# MCU.net
KiCad netlist of a schematic drawn in Altium Designer
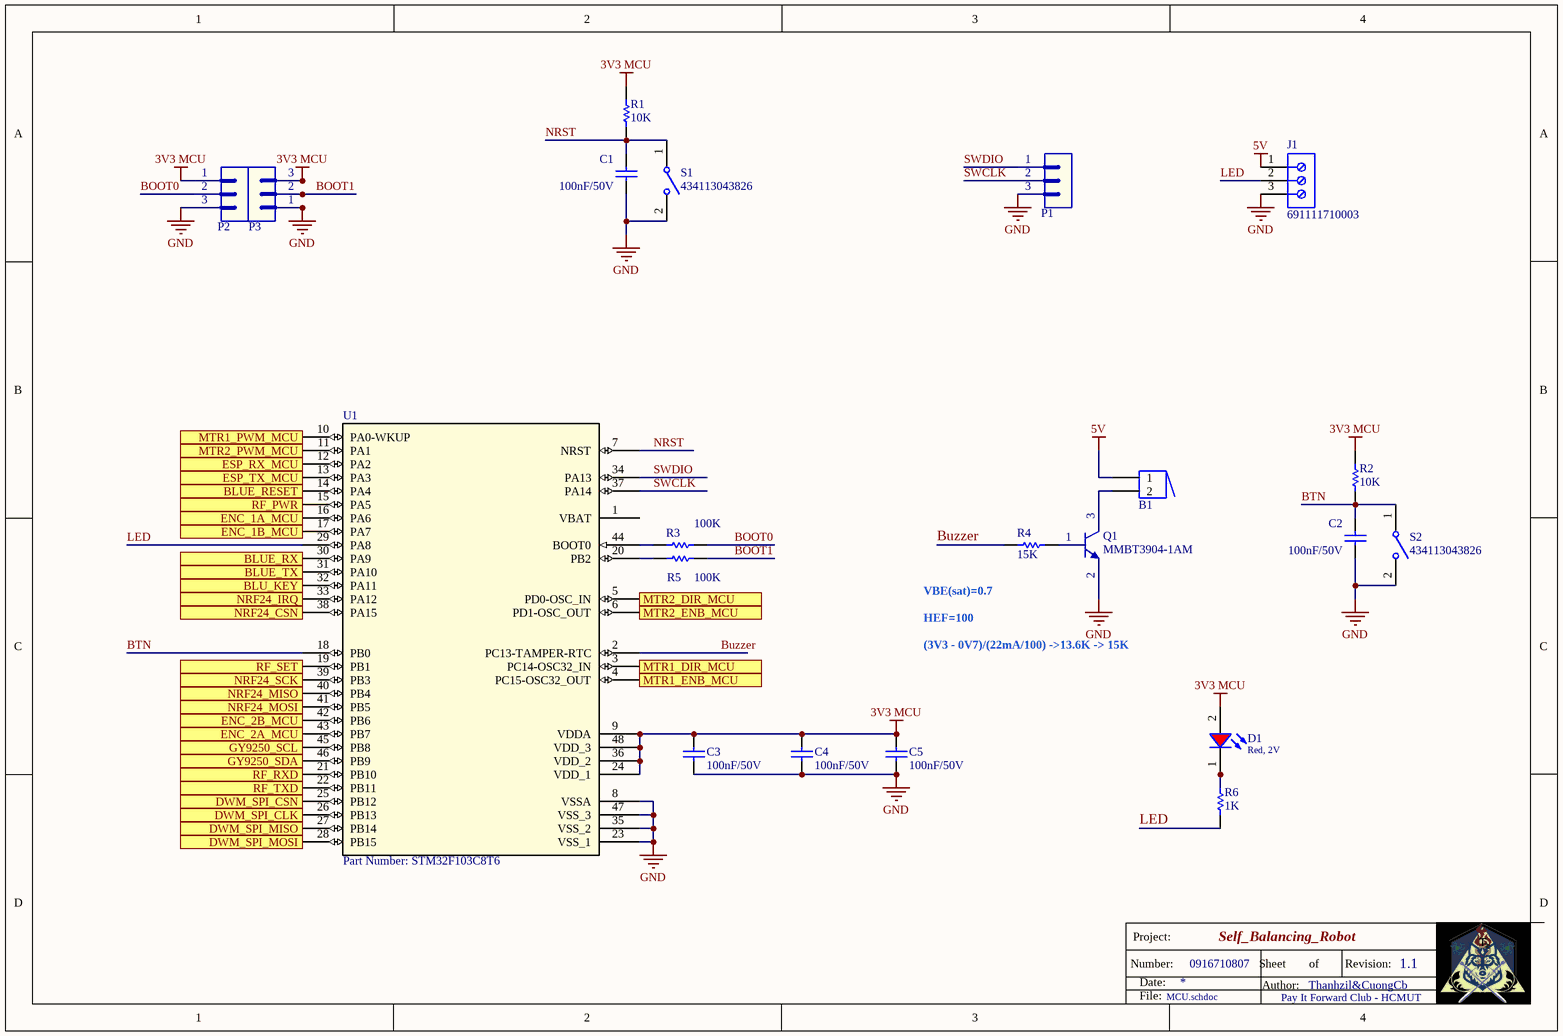
[diagram p0: MCU.SchDoc]

(export (version "E")
  (design (tool "Eeschema 10.0.6"))
  (components
    (comp (ref "B1")
      (value "Buzzer")
      (footprint "BUZZER")
      (libsource (lib "PIF_Schematic_Lib") (part "Buzzer"))
    )
    (comp (ref "C1")
      (value "100nF/50V")
      (footprint "CAP-SM-0805")
      (description "CAP CER 0.1UF 50V Y5V 0805")
      (fields
        (field (name "MANUFACTURER") "Samsung Electro-Mechanics")
        (field (name "MANUFACTURER PART NUMBER") "CL21F104ZBCNNNC")
      )
      (libsource (lib "Capacitor") (part "Cap-100nF-50V-0805"))
    )
    (comp (ref "C2")
      (value "100nF/50V")
      (footprint "CAP-SM-0805")
      (description "CAP CER 0.1UF 50V Y5V 0805")
      (fields
        (field (name "MANUFACTURER") "Samsung Electro-Mechanics")
        (field (name "MANUFACTURER PART NUMBER") "CL21F104ZBCNNNC")
      )
      (libsource (lib "Capacitor") (part "Cap-100nF-50V-0805"))
    )
    (comp (ref "C3")
      (value "100nF/50V")
      (footprint "CAP-SM-0805")
      (description "CAP CER 0.1UF 50V Y5V 0805")
      (fields
        (field (name "MANUFACTURER") "Samsung Electro-Mechanics")
        (field (name "MANUFACTURER PART NUMBER") "CL21F104ZBCNNNC")
      )
      (libsource (lib "Capacitor") (part "Cap-100nF-50V-0805"))
    )
    (comp (ref "C4")
      (value "100nF/50V")
      (footprint "CAP-SM-0805")
      (description "CAP CER 0.1UF 50V Y5V 0805")
      (fields
        (field (name "MANUFACTURER") "Samsung Electro-Mechanics")
        (field (name "MANUFACTURER PART NUMBER") "CL21F104ZBCNNNC")
      )
      (libsource (lib "Capacitor") (part "Cap-100nF-50V-0805"))
    )
    (comp (ref "C5")
      (value "100nF/50V")
      (footprint "CAP-SM-0805")
      (description "CAP CER 0.1UF 50V Y5V 0805")
      (fields
        (field (name "MANUFACTURER") "Samsung Electro-Mechanics")
        (field (name "MANUFACTURER PART NUMBER") "CL21F104ZBCNNNC")
      )
      (libsource (lib "Capacitor") (part "Cap-100nF-50V-0805"))
    )
    (comp (ref "D1")
      (value "Red, 2V")
      (footprint "WL-SMCW_0805")
      (description "WL-SMCW SMT Mono-color Chip LED Waterclear, size 0805, Red, 2V, 140deg")
      (fields (field (name "PART NUMBER") "150080RS75000") (field (name "PUBLISHER") "Wurth Elektronik"))
      (libsource (lib "LED_150060BS75000_Altium_WL-SMCW_rev20a") (part "150080RS75000"))
    )
    (comp (ref "J1")
      (value "691111710003")
      (footprint "Project_Xe_Can_Bang:691111710003")
      (description "WR-TBL Serie 111 Horizontal Entry Modular, Pressure Clamp, pitch 5mm, 3p")
      (fields (field (name "PUBLISHER") "Wurth Elektronik"))
      (libsource (lib "Project_Xe_Can_Bang") (part "691111710003"))
    )
    (comp (ref "P1")
      (value "Header 3")
      (footprint "Project_Xe_Can_Bang:JP3")
      (description "Header, 3-Pin")
      (fields (field (name "PUBLISHER") "Altium Limited"))
      (libsource (lib "Project_Xe_Can_Bang") (part "Header 3"))
    )
    (comp (ref "P2")
      (value "Header 3")
      (footprint "JP3")
      (description "Header, 3-Pin")
      (fields (field (name "PUBLISHER") "Altium Limited"))
      (libsource (lib "Header-connector") (part "Header 3"))
    )
    (comp (ref "P3")
      (value "Header 3")
      (footprint "JP3")
      (description "Header, 3-Pin")
      (fields (field (name "PUBLISHER") "Altium Limited"))
      (libsource (lib "") (part "Header 3_1"))
    )
    (comp (ref "Q1")
      (value "MMBT3904-1AM")
      (footprint "SOT23_NEX")
      (libsource (lib "BJT") (part "MMBT3904-1AM"))
    )
    (comp (ref "R1")
      (value "10K")
      (footprint "Resistor:RES-SM-0805")
      (description "RES 10K OHM 1% 1/4W 0805")
      (fields
        (field (name "MANUFACTURER") "Stackpole Electronics Inc")
        (field (name "MANUFACTURER PART NUMBER") "RNCP0805FTD10K0")
      )
      (libsource (lib "Resistor") (part "Res-10k-0805"))
    )
    (comp (ref "R2")
      (value "10K")
      (footprint "Resistor:RES-SM-0805")
      (description "RES 10K OHM 1% 1/4W 0805")
      (fields
        (field (name "MANUFACTURER") "Stackpole Electronics Inc")
        (field (name "MANUFACTURER PART NUMBER") "RNCP0805FTD10K0")
      )
      (libsource (lib "Resistor") (part "Res-10k-0805"))
    )
    (comp (ref "R3")
      (value "100K")
      (footprint "Resistor:RES-SM-0805")
      (description "RES 0 OHM JUMPER 0805")
      (fields
        (field (name "MANUFACTURER") "Vishay Dale")
        (field (name "MANUFACTURER PART NUMBER") "WSL080500000ZEA9")
      )
      (libsource (lib "Resistor") (part "Res-100K-0805"))
    )
    (comp (ref "R4")
      (value "15K")
      (footprint "Resistor:RES-SM-0805")
      (description "RES 15K OHM 1% 1/4W 0805")
      (fields
        (field (name "MANUFACTURER") "TE Connectivity Passive Product")
        (field (name "MANUFACTURER PART NUMBER") "CRGCQ0805F15K")
      )
      (libsource (lib "Resistor") (part "Res-15K-0805"))
    )
    (comp (ref "R5")
      (value "100K")
      (footprint "Resistor:RES-SM-0805")
      (description "RES 0 OHM JUMPER 0805")
      (fields
        (field (name "MANUFACTURER") "Vishay Dale")
        (field (name "MANUFACTURER PART NUMBER") "WSL080500000ZEA9")
      )
      (libsource (lib "Resistor") (part "Res-100K-0805"))
    )
    (comp (ref "R6")
      (value "1K")
      (footprint "Resistor:RES-SM-0805")
      (description "RES 1K OHM 1% 1/4W 0805")
      (fields
        (field (name "MANUFACTURER") "Stackpole Electronics Inc")
        (field (name "MANUFACTURER PART NUMBER") "RNCP0805FTD1K00")
      )
      (libsource (lib "Resistor") (part "Res-1K-0805"))
    )
    (comp (ref "S1")
      (value "434113043826")
      (footprint "434113043826")
      (description "WS-TASV J-Bend SMT Tact Switch 6x3.5mm, height 4.3mm, 260gf")
      (fields (field (name "PUBLISHER") "Wurth Elektronik"))
      (libsource (lib "434113043826_Altium_WS-TASV_rev20a") (part "434113043826"))
    )
    (comp (ref "S2")
      (value "434113043826")
      (footprint "434113043826")
      (description "WS-TASV J-Bend SMT Tact Switch 6x3.5mm, height 4.3mm, 260gf")
      (fields (field (name "PUBLISHER") "Wurth Elektronik"))
      (libsource (lib "434113043826_Altium_WS-TASV_rev20a") (part "434113043826"))
    )
    (comp (ref "U1")
      (value "Part Number: STM32F103C8T6")
      (footprint "Project_Xe_Can_Bang:LQFP - 48")
      (fields
        (field (name "MANUFACTURER_PART_NUMBER") "STM32F103C8T6")
        (field (name "COPYRIGHT") "Copyright (C) 2018 Accelerated Designs. All rights reserved")
      )
      (libsource (lib "Project_Xe_Can_Bang") (part "STM32F103C8T6"))
    )
  )
  (nets
    (net (code "2") (name "/BLUE_RESET") (class "Default")
      (node (ref "U1") (pin "14") (pinfunction "PA4_14") (pintype "bidirectional"))
    )
    (net (code "3") (name "/BLUE_RX") (class "Default")
      (node (ref "U1") (pin "30") (pinfunction "PA9_30") (pintype "bidirectional"))
    )
    (net (code "4") (name "/BLUE_TX") (class "Default")
      (node (ref "U1") (pin "31") (pinfunction "PA10_31") (pintype "bidirectional"))
    )
    (net (code "5") (name "/BLU_KEY") (class "Default")
      (node (ref "U1") (pin "32") (pinfunction "PA11_32") (pintype "bidirectional"))
    )
    (net (code "6") (name "/BOOT0") (class "Default")
      (node (ref "P2") (pin "2") (pinfunction "2_2") (pintype "passive"))
      (node (ref "R3") (pin "2") (pinfunction "2_2") (pintype "passive"))
    )
    (net (code "7") (name "/BOOT1") (class "Default")
      (node (ref "P3") (pin "2") (pinfunction "2_2") (pintype "passive"))
      (node (ref "R5") (pin "2") (pinfunction "2_2") (pintype "passive"))
    )
    (net (code "8") (name "/BTN") (class "Default")
      (node (ref "C2") (pin "2") (pinfunction "2_2") (pintype "passive"))
      (node (ref "R2") (pin "1") (pinfunction "1_1") (pintype "passive"))
      (node (ref "S2") (pin "1") (pinfunction "1_1") (pintype "passive"))
      (node (ref "U1") (pin "18") (pinfunction "PB0_18") (pintype "bidirectional"))
    )
    (net (code "9") (name "/Buzzer") (class "Default")
      (node (ref "R4") (pin "1") (pinfunction "1_1") (pintype "passive"))
      (node (ref "U1") (pin "2") (pinfunction "PC13-TAMPER-RTC_2") (pintype "bidirectional"))
    )
    (net (code "10") (name "/DWM_SPI_CLK") (class "Default")
      (node (ref "U1") (pin "26") (pinfunction "PB13_26") (pintype "bidirectional"))
    )
    (net (code "11") (name "/DWM_SPI_CSN") (class "Default")
      (node (ref "U1") (pin "25") (pinfunction "PB12_25") (pintype "bidirectional"))
    )
    (net (code "12") (name "/DWM_SPI_MISO") (class "Default")
      (node (ref "U1") (pin "27") (pinfunction "PB14_27") (pintype "bidirectional"))
    )
    (net (code "13") (name "/DWM_SPI_MOSI") (class "Default")
      (node (ref "U1") (pin "28") (pinfunction "PB15_28") (pintype "bidirectional"))
    )
    (net (code "14") (name "/ENC_1A_MCU") (class "Default")
      (node (ref "U1") (pin "16") (pinfunction "PA6_16") (pintype "bidirectional"))
    )
    (net (code "15") (name "/ENC_1B_MCU") (class "Default")
      (node (ref "U1") (pin "17") (pinfunction "PA7_17") (pintype "bidirectional"))
    )
    (net (code "16") (name "/ENC_2A_MCU") (class "Default")
      (node (ref "U1") (pin "43") (pinfunction "PB7_43") (pintype "bidirectional"))
    )
    (net (code "17") (name "/ENC_2B_MCU") (class "Default")
      (node (ref "U1") (pin "42") (pinfunction "PB6_42") (pintype "bidirectional"))
    )
    (net (code "18") (name "/ESP_RX_MCU") (class "Default")
      (node (ref "U1") (pin "12") (pinfunction "PA2_12") (pintype "bidirectional"))
    )
    (net (code "19") (name "/ESP_TX_MCU") (class "Default")
      (node (ref "U1") (pin "13") (pinfunction "PA3_13") (pintype "bidirectional"))
    )
    (net (code "20") (name "/GY9250_SCL") (class "Default")
      (node (ref "U1") (pin "45") (pinfunction "PB8_45") (pintype "bidirectional"))
    )
    (net (code "21") (name "/GY9250_SDA") (class "Default")
      (node (ref "U1") (pin "46") (pinfunction "PB9_46") (pintype "bidirectional"))
    )
    (net (code "23") (name "/LED") (class "Default")
      (node (ref "J1") (pin "2") (pinfunction "2_2") (pintype "passive"))
      (node (ref "R6") (pin "1") (pinfunction "1_1") (pintype "passive"))
      (node (ref "U1") (pin "29") (pinfunction "PA8_29") (pintype "bidirectional"))
    )
    (net (code "24") (name "/MTR1_DIR_MCU") (class "Default")
      (node (ref "U1") (pin "3") (pinfunction "PC14-OSC32_IN_3") (pintype "bidirectional"))
    )
    (net (code "25") (name "/MTR1_ENB_MCU") (class "Default")
      (node (ref "U1") (pin "4") (pinfunction "PC15-OSC32_OUT_4") (pintype "bidirectional"))
    )
    (net (code "26") (name "/MTR1_PWM_MCU") (class "Default")
      (node (ref "U1") (pin "10") (pinfunction "PA0-WKUP_10") (pintype "bidirectional"))
    )
    (net (code "27") (name "/MTR2_DIR_MCU") (class "Default")
      (node (ref "U1") (pin "5") (pinfunction "PD0-OSC_IN_5") (pintype "bidirectional"))
    )
    (net (code "28") (name "/MTR2_ENB_MCU") (class "Default")
      (node (ref "U1") (pin "6") (pinfunction "PD1-OSC_OUT_6") (pintype "bidirectional"))
    )
    (net (code "29") (name "/MTR2_PWM_MCU") (class "Default")
      (node (ref "U1") (pin "11") (pinfunction "PA1_11") (pintype "bidirectional"))
    )
    (net (code "30") (name "/NRF24_CSN") (class "Default")
      (node (ref "U1") (pin "38") (pinfunction "PA15_38") (pintype "bidirectional"))
    )
    (net (code "31") (name "/NRF24_IRQ") (class "Default")
      (node (ref "U1") (pin "33") (pinfunction "PA12_33") (pintype "bidirectional"))
    )
    (net (code "32") (name "/NRF24_MISO") (class "Default")
      (node (ref "U1") (pin "40") (pinfunction "PB4_40") (pintype "bidirectional"))
    )
    (net (code "33") (name "/NRF24_MOSI") (class "Default")
      (node (ref "U1") (pin "41") (pinfunction "PB5_41") (pintype "bidirectional"))
    )
    (net (code "34") (name "/NRF24_SCK") (class "Default")
      (node (ref "U1") (pin "39") (pinfunction "PB3_39") (pintype "bidirectional"))
    )
    (net (code "35") (name "/NRST") (class "Default")
      (node (ref "C1") (pin "2") (pinfunction "2_2") (pintype "passive"))
      (node (ref "R1") (pin "1") (pinfunction "1_1") (pintype "passive"))
      (node (ref "S1") (pin "1") (pinfunction "1_1") (pintype "passive"))
      (node (ref "U1") (pin "7") (pinfunction "NRST_7") (pintype "bidirectional"))
    )
    (net (code "36") (name "/RF_PWR") (class "Default")
      (node (ref "U1") (pin "15") (pinfunction "PA5_15") (pintype "bidirectional"))
    )
    (net (code "37") (name "/RF_RXD") (class "Default")
      (node (ref "U1") (pin "21") (pinfunction "PB10_21") (pintype "bidirectional"))
    )
    (net (code "38") (name "/RF_SET") (class "Default")
      (node (ref "U1") (pin "19") (pinfunction "PB1_19") (pintype "bidirectional"))
    )
    (net (code "39") (name "/RF_TXD") (class "Default")
      (node (ref "U1") (pin "22") (pinfunction "PB11_22") (pintype "bidirectional"))
    )
    (net (code "40") (name "/SWCLK") (class "Default")
      (node (ref "P1") (pin "2") (pinfunction "2_2") (pintype "passive"))
      (node (ref "U1") (pin "37") (pinfunction "PA14_37") (pintype "bidirectional"))
    )
    (net (code "41") (name "/SWDIO") (class "Default")
      (node (ref "P1") (pin "1") (pinfunction "1_1") (pintype "passive"))
      (node (ref "U1") (pin "34") (pinfunction "PA13_34") (pintype "bidirectional"))
    )
    (net (code "43") (name "3V3 MCU") (class "Default")
      (node (ref "C3") (pin "2") (pinfunction "2_2") (pintype "passive"))
      (node (ref "C4") (pin "1") (pinfunction "1_1") (pintype "passive"))
      (node (ref "C5") (pin "2") (pinfunction "2_2") (pintype "passive"))
      (node (ref "D1") (pin "2") (pinfunction "A_2") (pintype "passive"))
      (node (ref "P2") (pin "1") (pinfunction "1_1") (pintype "passive"))
      (node (ref "P3") (pin "3") (pinfunction "3_3") (pintype "passive"))
      (node (ref "R1") (pin "2") (pinfunction "2_2") (pintype "passive"))
      (node (ref "R2") (pin "2") (pinfunction "2_2") (pintype "passive"))
      (node (ref "U1") (pin "24") (pinfunction "VDD_1_24") (pintype "power_in"))
      (node (ref "U1") (pin "36") (pinfunction "VDD_2_36") (pintype "power_in"))
      (node (ref "U1") (pin "48") (pinfunction "VDD_3_48") (pintype "power_in"))
      (node (ref "U1") (pin "9") (pinfunction "VDDA_9") (pintype "power_in"))
    )
    (net (code "44") (name "5V") (class "Default")
      (node (ref "B1") (pin "1") (pinfunction "1_1") (pintype "passive"))
      (node (ref "J1") (pin "1") (pinfunction "1_1") (pintype "passive"))
    )
    (net (code "45") (name "GND") (class "Default")
      (node (ref "C1") (pin "1") (pinfunction "1_1") (pintype "passive"))
      (node (ref "C2") (pin "1") (pinfunction "1_1") (pintype "passive"))
      (node (ref "C3") (pin "1") (pinfunction "1_1") (pintype "passive"))
      (node (ref "C4") (pin "2") (pinfunction "2_2") (pintype "passive"))
      (node (ref "C5") (pin "1") (pinfunction "1_1") (pintype "passive"))
      (node (ref "J1") (pin "3") (pinfunction "3_3") (pintype "passive"))
      (node (ref "P1") (pin "3") (pinfunction "3_3") (pintype "passive"))
      (node (ref "P2") (pin "3") (pinfunction "3_3") (pintype "passive"))
      (node (ref "P3") (pin "1") (pinfunction "1_1") (pintype "passive"))
      (node (ref "Q1") (pin "2") (pinfunction "E_2") (pintype "passive"))
      (node (ref "S1") (pin "2") (pinfunction "2_2") (pintype "passive"))
      (node (ref "S2") (pin "2") (pinfunction "2_2") (pintype "passive"))
      (node (ref "U1") (pin "23") (pinfunction "VSS_1_23") (pintype "power_in"))
      (node (ref "U1") (pin "35") (pinfunction "VSS_2_35") (pintype "power_in"))
      (node (ref "U1") (pin "47") (pinfunction "VSS_3_47") (pintype "power_in"))
      (node (ref "U1") (pin "8") (pinfunction "VSSA_8") (pintype "power_in"))
    )
    (net (code "46") (name "Net-(D1-K)") (class "Default")
      (node (ref "D1") (pin "1") (pinfunction "K_1") (pintype "passive"))
      (node (ref "R6") (pin "2") (pinfunction "2_2") (pintype "passive"))
    )
    (net (code "47") (name "Net-(Q1-B)") (class "Default")
      (node (ref "Q1") (pin "1") (pinfunction "B_1") (pintype "passive"))
      (node (ref "R4") (pin "2") (pinfunction "2_2") (pintype "passive"))
    )
    (net (code "48") (name "Net-(Q1-C)") (class "Default")
      (node (ref "B1") (pin "2") (pinfunction "2_2") (pintype "passive"))
      (node (ref "Q1") (pin "3") (pinfunction "C_3") (pintype "passive"))
    )
    (net (code "49") (name "Net-(U1-BOOT0)") (class "Default")
      (node (ref "R3") (pin "1") (pinfunction "1_1") (pintype "passive"))
      (node (ref "U1") (pin "44") (pinfunction "BOOT0_44") (pintype "input"))
    )
    (net (code "50") (name "Net-(U1-PB2)") (class "Default")
      (node (ref "R5") (pin "1") (pinfunction "1_1") (pintype "passive"))
      (node (ref "U1") (pin "20") (pinfunction "PB2_20") (pintype "bidirectional"))
    )
    (net (code "51") (name "unconnected-(U1-VBAT-Pad1)") (class "Default")
      (node (ref "U1") (pin "1") (pinfunction "VBAT_1") (pintype "power_in"))
    )
  )
)
